# bmsMaster_isospi.net
KiCad netlist of a schematic drawn in Altium Designer
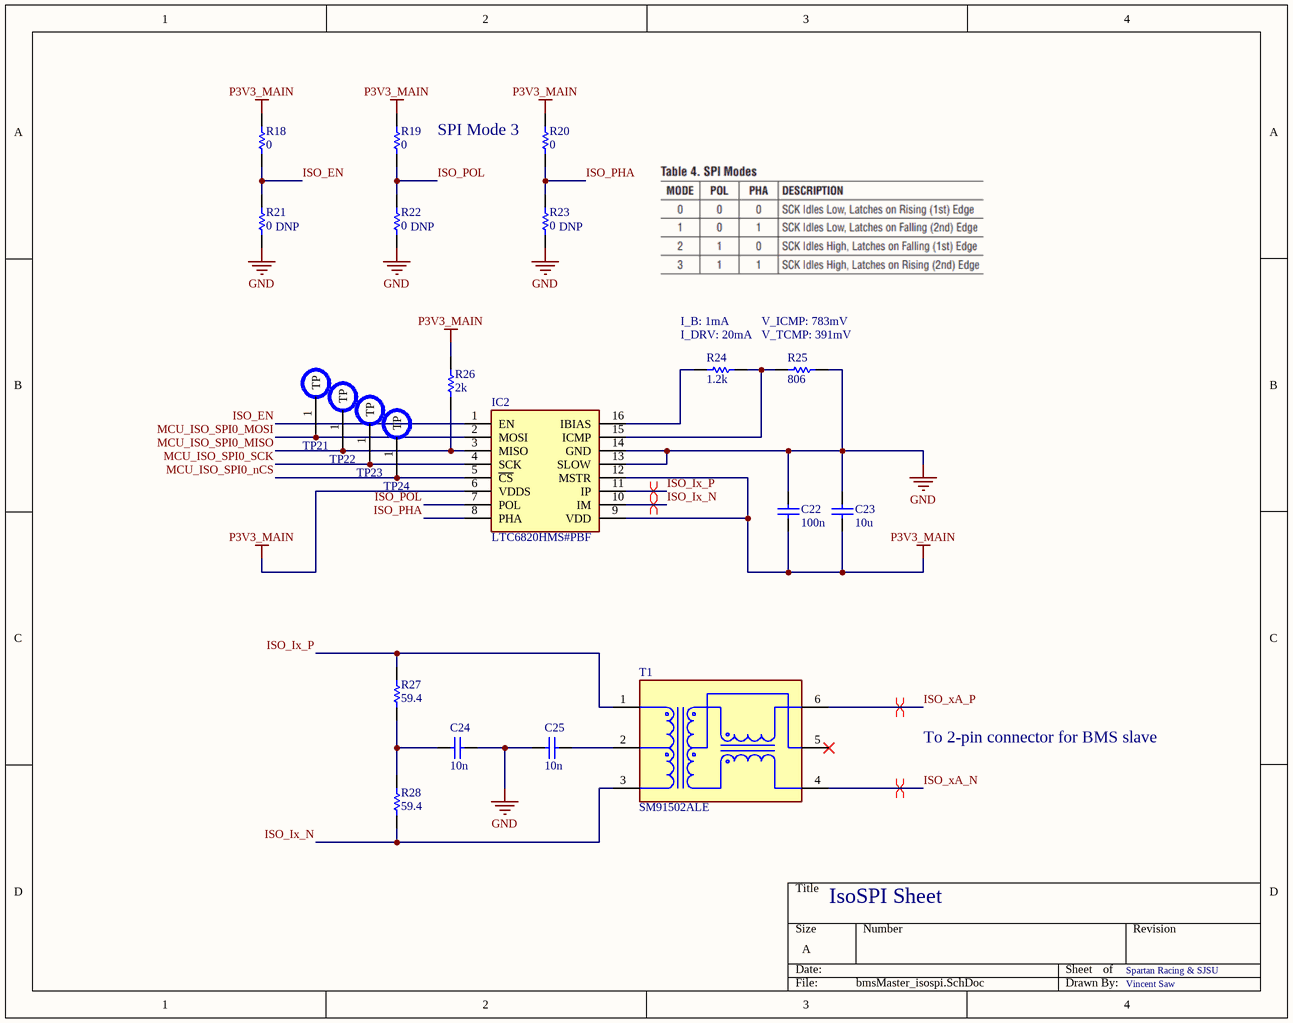
[diagram p0: bmsMaster_isospi.SchDoc]

(export (version "E")
  (design (tool "Eeschema 10.0.6"))
  (components
    (comp (ref "C22")
      (value "100n")
      (footprint "CAPC1608X90N")
      (description "Capacitor")
      (libsource (lib "Simulation Generic Components") (part "Capacitor"))
    )
    (comp (ref "C23")
      (value "10u")
      (footprint "CAPC1608X90N")
      (description "Capacitor")
      (libsource (lib "Simulation Generic Components") (part "Capacitor"))
    )
    (comp (ref "C24")
      (value "10n")
      (footprint "CAPC1608X90N")
      (description "Capacitor")
      (libsource (lib "Simulation Generic Components") (part "Capacitor"))
    )
    (comp (ref "C25")
      (value "10n")
      (footprint "CAPC1608X90N")
      (description "Capacitor")
      (libsource (lib "Simulation Generic Components") (part "Capacitor"))
    )
    (comp (ref "IC2")
      (value "LTC6820HMS#PBF")
      (footprint "SamacSys:SOP50P490X110-16N")
      (description "Integrated Circuit")
      (fields (field (name "MOUSER PART NUMBER") "584-LTC6820HMS#PBF"))
      (libsource (lib "*") (part "LTC6820HMS#PBF"))
    )
    (comp (ref "R18")
      (value "0")
      (footprint "RESC1608X50N")
      (description "Resistor")
      (libsource (lib "Simulation Generic Components") (part "Resistor"))
    )
    (comp (ref "R19")
      (value "0")
      (footprint "RESC1608X50N")
      (description "Resistor")
      (libsource (lib "Simulation Generic Components") (part "Resistor"))
    )
    (comp (ref "R20")
      (value "0")
      (footprint "RESC1608X50N")
      (description "Resistor")
      (libsource (lib "Simulation Generic Components") (part "Resistor"))
    )
    (comp (ref "R21")
      (value "0")
      (footprint "RESC1608X50N")
      (description "Resistor")
      (libsource (lib "Simulation Generic Components") (part "Resistor"))
    )
    (comp (ref "R22")
      (value "0")
      (footprint "RESC1608X50N")
      (description "Resistor")
      (libsource (lib "Simulation Generic Components") (part "Resistor"))
    )
    (comp (ref "R23")
      (value "0")
      (footprint "RESC1608X50N")
      (description "Resistor")
      (libsource (lib "Simulation Generic Components") (part "Resistor"))
    )
    (comp (ref "R24")
      (value "1.2k")
      (footprint "RESC1608X50N")
      (description "Resistor")
      (libsource (lib "Simulation Generic Components") (part "Resistor"))
    )
    (comp (ref "R25")
      (value "806")
      (footprint "RESC1608X50N")
      (description "Resistor")
      (libsource (lib "Simulation Generic Components") (part "Resistor"))
    )
    (comp (ref "R26")
      (value "2k")
      (footprint "RESC1608X50N")
      (description "Resistor")
      (libsource (lib "Simulation Generic Components") (part "Resistor"))
    )
    (comp (ref "R27")
      (value "59.4")
      (footprint "RESC1608X50N")
      (description "Resistor")
      (libsource (lib "Simulation Generic Components") (part "Resistor"))
    )
    (comp (ref "R28")
      (value "59.4")
      (footprint "RESC1608X50N")
      (description "Resistor")
      (libsource (lib "Simulation Generic Components") (part "Resistor"))
    )
    (comp (ref "T1")
      (value "SM91502ALE")
      (footprint "FP-SM91502ALE-MFG")
      (description "BMS XFORMER 1-CH 1000V AECQ +125")
      (fields
        (field (name "MANUFACTURER") "Bourns")
        (field (name "OCTOPART") "https://octopart.com/sm91502ale-bourns-95732123")
      )
      (libsource (lib "Altium Content Vault") (part "554ff5199021d68917f526d8699f58a"))
    )
    (comp (ref "TP21")
      (value "TSTPT")
      (footprint "Testpoint1")
      (libsource (lib "testpoint1") (part "Testpoint1"))
    )
    (comp (ref "TP22")
      (value "TSTPT")
      (footprint "Testpoint1")
      (libsource (lib "testpoint1") (part "Testpoint1"))
    )
    (comp (ref "TP23")
      (value "TSTPT")
      (footprint "Testpoint1")
      (libsource (lib "testpoint1") (part "Testpoint1"))
    )
    (comp (ref "TP24")
      (value "TSTPT")
      (footprint "Testpoint1")
      (libsource (lib "testpoint1") (part "Testpoint1"))
    )
  )
  (nets
    (net (code "1") (name "/ISO_EN") (class "Default")
      (node (ref "IC2") (pin "1") (pinfunction "EN_1") (pintype "passive"))
      (node (ref "R18") (pin "1") (pinfunction "1_1") (pintype "passive"))
      (node (ref "R21") (pin "2") (pinfunction "2_2") (pintype "passive"))
    )
    (net (code "2") (name "/ISO_Ix_N") (class "Default")
      (node (ref "IC2") (pin "10") (pinfunction "IM_10") (pintype "passive"))
      (node (ref "R28") (pin "1") (pinfunction "1_1") (pintype "passive"))
      (node (ref "T1") (pin "3") (pinfunction "3_3") (pintype "passive"))
    )
    (net (code "3") (name "/ISO_Ix_P") (class "Default")
      (node (ref "IC2") (pin "11") (pinfunction "IP_11") (pintype "passive"))
      (node (ref "R27") (pin "2") (pinfunction "2_2") (pintype "passive"))
      (node (ref "T1") (pin "1") (pinfunction "1_1") (pintype "passive"))
    )
    (net (code "4") (name "/ISO_PHA") (class "Default")
      (node (ref "IC2") (pin "8") (pinfunction "PHA_8") (pintype "passive"))
      (node (ref "R20") (pin "1") (pinfunction "1_1") (pintype "passive"))
      (node (ref "R23") (pin "2") (pinfunction "2_2") (pintype "passive"))
    )
    (net (code "5") (name "/ISO_POL") (class "Default")
      (node (ref "IC2") (pin "7") (pinfunction "POL_7") (pintype "passive"))
      (node (ref "R19") (pin "1") (pinfunction "1_1") (pintype "passive"))
      (node (ref "R22") (pin "2") (pinfunction "2_2") (pintype "passive"))
    )
    (net (code "6") (name "/ISO_xA_N") (class "Default")
      (node (ref "T1") (pin "4") (pinfunction "4_4") (pintype "passive"))
    )
    (net (code "7") (name "/ISO_xA_P") (class "Default")
      (node (ref "T1") (pin "6") (pinfunction "6_6") (pintype "passive"))
    )
    (net (code "8") (name "/MCU_ISO_SPI0_MISO") (class "Default")
      (node (ref "IC2") (pin "3") (pinfunction "MISO_3") (pintype "passive"))
      (node (ref "R26") (pin "1") (pinfunction "1_1") (pintype "passive"))
      (node (ref "TP22") (pin "1") (pinfunction "TP_1") (pintype "passive"))
    )
    (net (code "9") (name "/MCU_ISO_SPI0_MOSI") (class "Default")
      (node (ref "IC2") (pin "2") (pinfunction "MOSI_2") (pintype "passive"))
      (node (ref "TP21") (pin "1") (pinfunction "TP_1") (pintype "passive"))
    )
    (net (code "10") (name "/MCU_ISO_SPI0_SCK") (class "Default")
      (node (ref "IC2") (pin "4") (pinfunction "SCK_4") (pintype "passive"))
      (node (ref "TP23") (pin "1") (pinfunction "TP_1") (pintype "passive"))
    )
    (net (code "11") (name "/MCU_ISO_SPI0_nCS") (class "Default")
      (node (ref "IC2") (pin "5") (pinfunction "~{CS}_5") (pintype "passive"))
      (node (ref "TP24") (pin "1") (pinfunction "TP_1") (pintype "passive"))
    )
    (net (code "12") (name "GND") (class "Default")
      (node (ref "C22") (pin "2") (pinfunction "2_2") (pintype "passive"))
      (node (ref "C23") (pin "2") (pinfunction "2_2") (pintype "passive"))
      (node (ref "C24") (pin "1") (pinfunction "1_1") (pintype "passive"))
      (node (ref "C25") (pin "1") (pinfunction "1_1") (pintype "passive"))
      (node (ref "IC2") (pin "13") (pinfunction "SLOW_13") (pintype "passive"))
      (node (ref "IC2") (pin "14") (pinfunction "GND_14") (pintype "passive"))
      (node (ref "R21") (pin "1") (pinfunction "1_1") (pintype "passive"))
      (node (ref "R22") (pin "1") (pinfunction "1_1") (pintype "passive"))
      (node (ref "R23") (pin "1") (pinfunction "1_1") (pintype "passive"))
      (node (ref "R25") (pin "2") (pinfunction "2_2") (pintype "passive"))
    )
    (net (code "13") (name "Net-(C24-Pad2)") (class "Default")
      (node (ref "C24") (pin "2") (pinfunction "2_2") (pintype "passive"))
      (node (ref "R27") (pin "1") (pinfunction "1_1") (pintype "passive"))
      (node (ref "R28") (pin "2") (pinfunction "2_2") (pintype "passive"))
    )
    (net (code "14") (name "Net-(C25-Pad2)") (class "Default")
      (node (ref "C25") (pin "2") (pinfunction "2_2") (pintype "passive"))
      (node (ref "T1") (pin "2") (pinfunction "2_2") (pintype "passive"))
    )
    (net (code "15") (name "Net-(IC2-IBIAS)") (class "Default")
      (node (ref "IC2") (pin "16") (pinfunction "IBIAS_16") (pintype "passive"))
      (node (ref "R24") (pin "1") (pinfunction "1_1") (pintype "passive"))
    )
    (net (code "16") (name "Net-(IC2-ICMP)") (class "Default")
      (node (ref "IC2") (pin "15") (pinfunction "ICMP_15") (pintype "passive"))
      (node (ref "R24") (pin "2") (pinfunction "2_2") (pintype "passive"))
      (node (ref "R25") (pin "1") (pinfunction "1_1") (pintype "passive"))
    )
    (net (code "17") (name "P3V3_MAIN") (class "Default")
      (node (ref "C22") (pin "1") (pinfunction "1_1") (pintype "passive"))
      (node (ref "C23") (pin "1") (pinfunction "1_1") (pintype "passive"))
      (node (ref "IC2") (pin "12") (pinfunction "MSTR_12") (pintype "passive"))
      (node (ref "IC2") (pin "6") (pinfunction "VDDS_6") (pintype "passive"))
      (node (ref "IC2") (pin "9") (pinfunction "VDD_9") (pintype "passive"))
      (node (ref "R18") (pin "2") (pinfunction "2_2") (pintype "passive"))
      (node (ref "R19") (pin "2") (pinfunction "2_2") (pintype "passive"))
      (node (ref "R20") (pin "2") (pinfunction "2_2") (pintype "passive"))
      (node (ref "R26") (pin "2") (pinfunction "2_2") (pintype "passive"))
    )
    (net (code "18") (name "unconnected-(T1-Pad5)") (class "Default")
      (node (ref "T1") (pin "5") (pinfunction "5_5") (pintype "passive+no_connect"))
    )
  )
)
